# Veroboard_for_ckt_designing_2.net
KiCad netlist of a schematic drawn in EAGLE
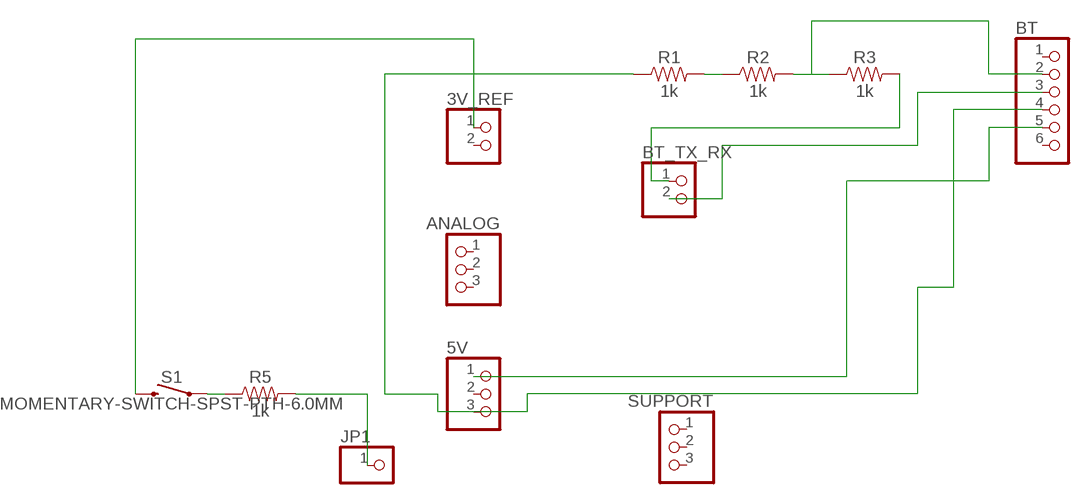
[diagram p0: schematic, sheet 2]

(export (version "E")
  (design (tool "Eeschema 10.0.6"))
  (components
    (comp (ref "3V_REF")
      (value "PINHD-1X2")
      (footprint "eagle-import:1X02")
      (libsource (lib "eagle-import") (part "PINHD-1X2"))
    )
    (comp (ref "5V")
      (value "PINHD-1X3")
      (footprint "eagle-import:1X03")
      (libsource (lib "eagle-import") (part "PINHD-1X3"))
    )
    (comp (ref "ANALOG")
      (value "PINHD-1X3")
      (footprint "eagle-import:1X03")
      (libsource (lib "eagle-import") (part "PINHD-1X3"))
    )
    (comp (ref "BT")
      (value "PINHD-1X6")
      (footprint "eagle-import:1X06")
      (libsource (lib "eagle-import") (part "PINHD-1X6"))
    )
    (comp (ref "BT_TX_RX")
      (value "PINHD-1X2")
      (footprint "eagle-import:1X02")
      (libsource (lib "eagle-import") (part "PINHD-1X2"))
    )
    (comp (ref "JP1")
      (value "PINHD-1X1")
      (footprint "eagle-import:1X01")
      (libsource (lib "eagle-import") (part "PINHD-1X1"))
    )
    (comp (ref "R1")
      (value "1k")
      (footprint "eagle-import:AXIAL-0.3")
      (libsource (lib "eagle-import") (part "1KOHM-HORIZ-1/4W-1%"))
    )
    (comp (ref "R2")
      (value "1k")
      (footprint "eagle-import:AXIAL-0.3")
      (libsource (lib "eagle-import") (part "1KOHM-HORIZ-1/4W-1%"))
    )
    (comp (ref "R3")
      (value "1k")
      (footprint "eagle-import:AXIAL-0.3")
      (libsource (lib "eagle-import") (part "1KOHM-HORIZ-1/4W-1%"))
    )
    (comp (ref "R5")
      (value "1k")
      (footprint "eagle-import:AXIAL-0.3")
      (libsource (lib "eagle-import") (part "1KOHM-HORIZ-1/4W-1%"))
    )
    (comp (ref "S1")
      (value "MOMENTARY-SWITCH-SPST-PTH-6.0MM")
      (footprint "eagle-import:TACTILE_SWITCH_PTH_6.0MM")
      (libsource (lib "eagle-import") (part "MOMENTARY-SWITCH-SPST-PTH-6.0MM"))
    )
    (comp (ref "SUPPORT")
      (value "PINHD-1X3")
      (footprint "eagle-import:1X03")
      (libsource (lib "eagle-import") (part "PINHD-1X3"))
    )
  )
  (nets
    (net (code "1") (name "Net-(5V-Pad1)") (class "Default")
      (node (ref "5V") (pin "1") (pinfunction "1_1") (pintype "passive"))
      (node (ref "BT") (pin "5") (pinfunction "5_5") (pintype "passive"))
    )
    (net (code "2") (name "Net-(BT-Pad3)") (class "Default")
      (node (ref "BT") (pin "3") (pinfunction "3_3") (pintype "passive"))
      (node (ref "BT_TX_RX") (pin "2") (pinfunction "2_2") (pintype "passive"))
    )
    (net (code "3") (name "Net-(R1-1)") (class "Default")
      (node (ref "5V") (pin "3") (pinfunction "3_3") (pintype "passive"))
      (node (ref "BT") (pin "4") (pinfunction "4_4") (pintype "passive"))
      (node (ref "R1") (pin "P$1") (pinfunction "1_P$1") (pintype "passive"))
    )
    (net (code "4") (name "Net-(R1-2)") (class "Default")
      (node (ref "R1") (pin "P$2") (pinfunction "2_P$2") (pintype "passive"))
      (node (ref "R2") (pin "P$1") (pinfunction "1_P$1") (pintype "passive"))
    )
    (net (code "5") (name "Net-(R2-2)") (class "Default")
      (node (ref "BT") (pin "2") (pinfunction "2_2") (pintype "passive"))
      (node (ref "R2") (pin "P$2") (pinfunction "2_P$2") (pintype "passive"))
      (node (ref "R3") (pin "P$1") (pinfunction "1_P$1") (pintype "passive"))
    )
    (net (code "6") (name "Net-(R3-2)") (class "Default")
      (node (ref "BT_TX_RX") (pin "1") (pinfunction "1_1") (pintype "passive"))
      (node (ref "R3") (pin "P$2") (pinfunction "2_P$2") (pintype "passive"))
    )
    (net (code "7") (name "Net-(R5-1)") (class "Default")
      (node (ref "R5") (pin "P$1") (pinfunction "1_P$1") (pintype "passive"))
      (node (ref "S1") (pin "1") (pinfunction "1_1") (pintype "passive"))
    )
    (net (code "8") (name "Net-(R5-2)") (class "Default")
      (node (ref "JP1") (pin "1") (pinfunction "1_1") (pintype "passive"))
      (node (ref "R5") (pin "P$2") (pinfunction "2_P$2") (pintype "passive"))
    )
    (net (code "9") (name "Net-(S1-2)") (class "Default")
      (node (ref "3V_REF") (pin "1") (pinfunction "1_1") (pintype "passive"))
      (node (ref "S1") (pin "3") (pinfunction "2_3") (pintype "passive"))
    )
    (net (code "10") (name "unconnected-(3V_REF-Pad2)") (class "Default")
      (node (ref "3V_REF") (pin "2") (pinfunction "2_2") (pintype "passive"))
    )
    (net (code "11") (name "unconnected-(5V-Pad2)") (class "Default")
      (node (ref "5V") (pin "2") (pinfunction "2_2") (pintype "passive"))
    )
    (net (code "12") (name "unconnected-(ANALOG-Pad1)") (class "Default")
      (node (ref "ANALOG") (pin "1") (pinfunction "1_1") (pintype "passive"))
    )
    (net (code "13") (name "unconnected-(ANALOG-Pad2)") (class "Default")
      (node (ref "ANALOG") (pin "2") (pinfunction "2_2") (pintype "passive"))
    )
    (net (code "14") (name "unconnected-(ANALOG-Pad3)") (class "Default")
      (node (ref "ANALOG") (pin "3") (pinfunction "3_3") (pintype "passive"))
    )
    (net (code "15") (name "unconnected-(BT-Pad1)") (class "Default")
      (node (ref "BT") (pin "1") (pinfunction "1_1") (pintype "passive"))
    )
    (net (code "16") (name "unconnected-(BT-Pad6)") (class "Default")
      (node (ref "BT") (pin "6") (pinfunction "6_6") (pintype "passive"))
    )
    (net (code "17") (name "unconnected-(SUPPORT-Pad1)") (class "Default")
      (node (ref "SUPPORT") (pin "1") (pinfunction "1_1") (pintype "passive"))
    )
    (net (code "18") (name "unconnected-(SUPPORT-Pad2)") (class "Default")
      (node (ref "SUPPORT") (pin "2") (pinfunction "2_2") (pintype "passive"))
    )
    (net (code "19") (name "unconnected-(SUPPORT-Pad3)") (class "Default")
      (node (ref "SUPPORT") (pin "3") (pinfunction "3_3") (pintype "passive"))
    )
  )
)
